# dumbpad.net
KiCad netlist of a schematic drawn in EAGLE
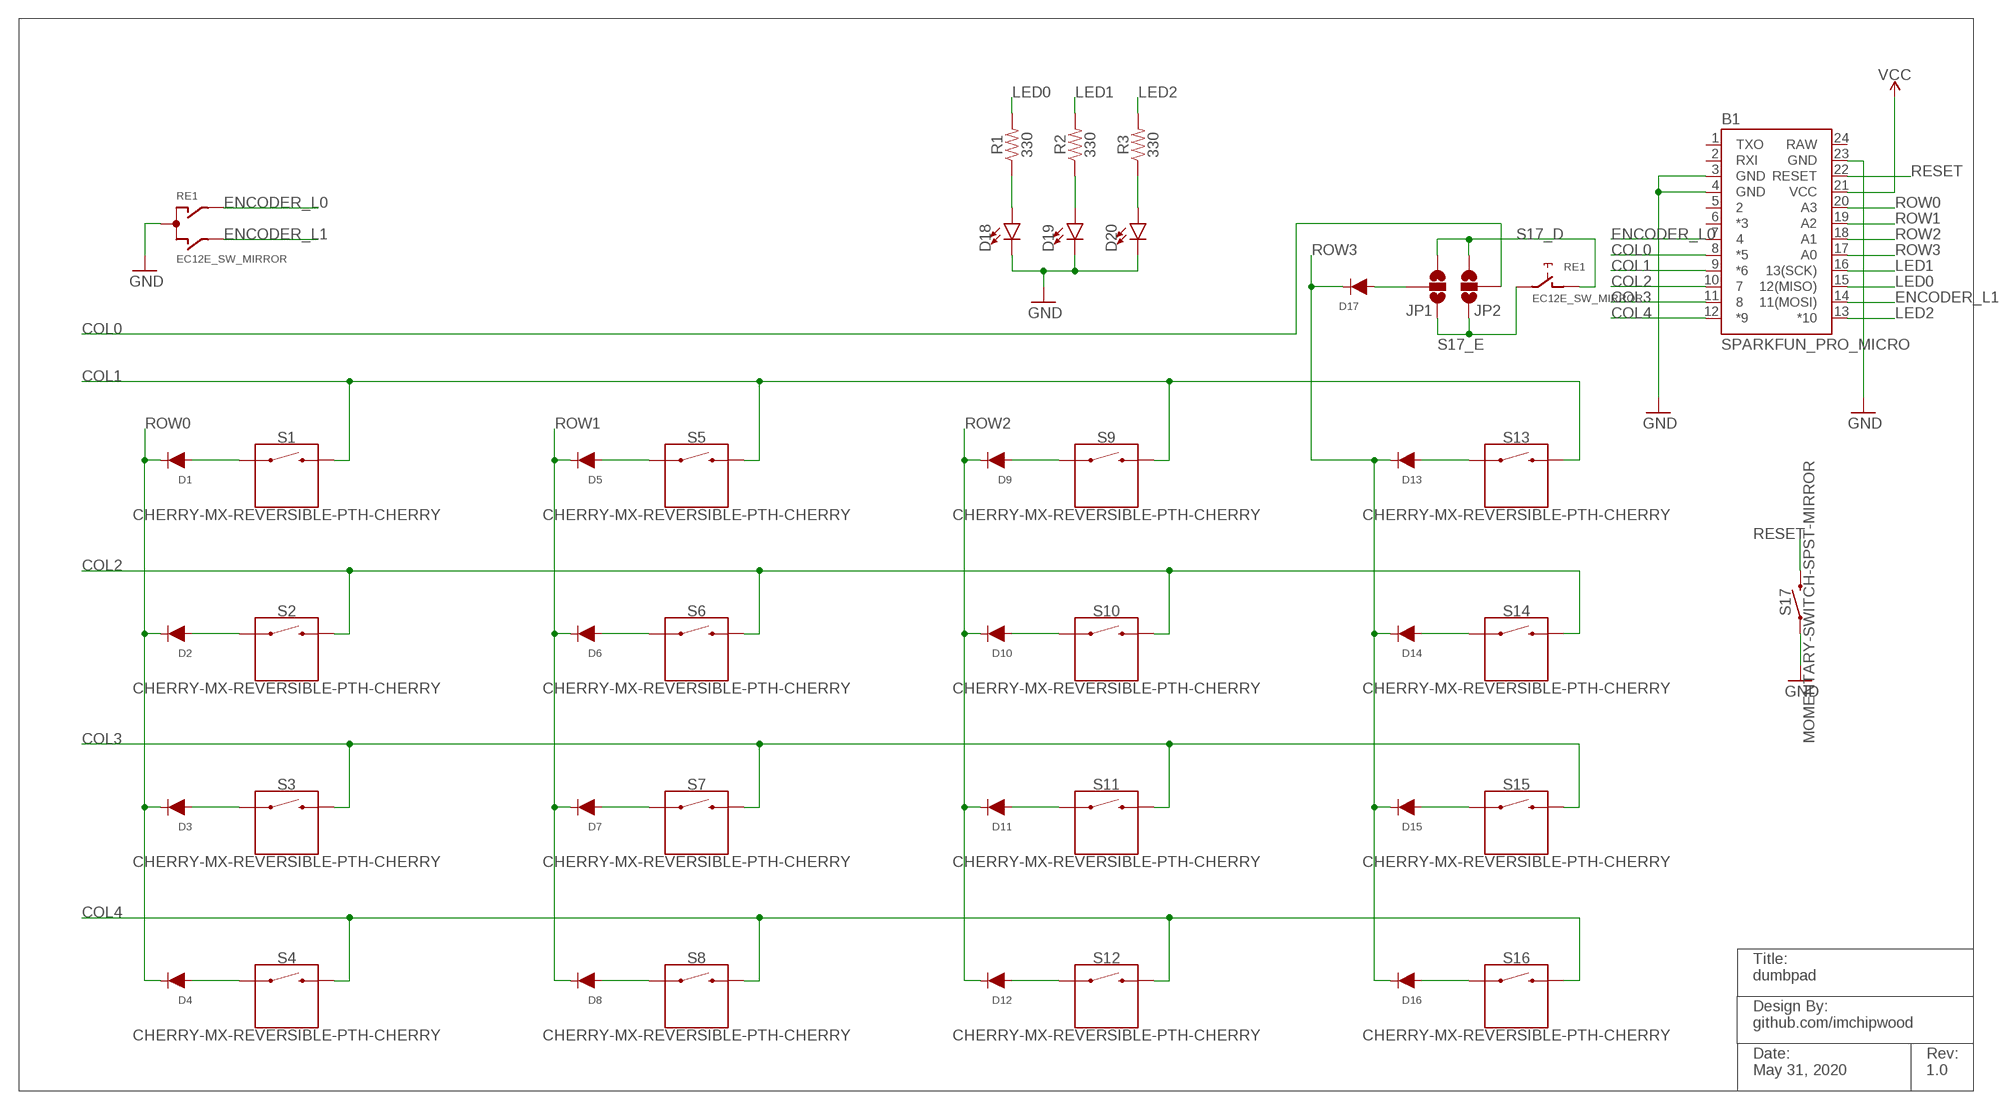
[diagram p0: schematic, sheet 1]

(export (version "E")
  (design (tool "Eeschema 10.0.6"))
  (components
    (comp (ref "B1")
      (value "SPARKFUN_PRO_MICRO")
      (footprint "eagle-import:SPARKFUN_PRO_MICRO")
      (libsource (lib "eagle-import") (part "SPARKFUN_PRO_MICRO"))
    )
    (comp (ref "D1")
      (value "DO-1N4148_MIRROR")
      (footprint "eagle-import:DO-1N4148_MIRROR")
      (libsource (lib "eagle-import") (part "DO-1N4148_MIRROR"))
    )
    (comp (ref "D2")
      (value "DO-1N4148_MIRROR")
      (footprint "eagle-import:DO-1N4148_MIRROR")
      (libsource (lib "eagle-import") (part "DO-1N4148_MIRROR"))
    )
    (comp (ref "D3")
      (value "DO-1N4148_MIRROR")
      (footprint "eagle-import:DO-1N4148_MIRROR")
      (libsource (lib "eagle-import") (part "DO-1N4148_MIRROR"))
    )
    (comp (ref "D4")
      (value "DO-1N4148_MIRROR")
      (footprint "eagle-import:DO-1N4148_MIRROR")
      (libsource (lib "eagle-import") (part "DO-1N4148_MIRROR"))
    )
    (comp (ref "D5")
      (value "DO-1N4148_MIRROR")
      (footprint "eagle-import:DO-1N4148_MIRROR")
      (libsource (lib "eagle-import") (part "DO-1N4148_MIRROR"))
    )
    (comp (ref "D6")
      (value "DO-1N4148_MIRROR")
      (footprint "eagle-import:DO-1N4148_MIRROR")
      (libsource (lib "eagle-import") (part "DO-1N4148_MIRROR"))
    )
    (comp (ref "D7")
      (value "DO-1N4148_MIRROR")
      (footprint "eagle-import:DO-1N4148_MIRROR")
      (libsource (lib "eagle-import") (part "DO-1N4148_MIRROR"))
    )
    (comp (ref "D8")
      (value "DO-1N4148_MIRROR")
      (footprint "eagle-import:DO-1N4148_MIRROR")
      (libsource (lib "eagle-import") (part "DO-1N4148_MIRROR"))
    )
    (comp (ref "D9")
      (value "DO-1N4148_MIRROR")
      (footprint "eagle-import:DO-1N4148_MIRROR")
      (libsource (lib "eagle-import") (part "DO-1N4148_MIRROR"))
    )
    (comp (ref "D10")
      (value "DO-1N4148_MIRROR")
      (footprint "eagle-import:DO-1N4148_MIRROR")
      (libsource (lib "eagle-import") (part "DO-1N4148_MIRROR"))
    )
    (comp (ref "D11")
      (value "DO-1N4148_MIRROR")
      (footprint "eagle-import:DO-1N4148_MIRROR")
      (libsource (lib "eagle-import") (part "DO-1N4148_MIRROR"))
    )
    (comp (ref "D12")
      (value "DO-1N4148_MIRROR")
      (footprint "eagle-import:DO-1N4148_MIRROR")
      (libsource (lib "eagle-import") (part "DO-1N4148_MIRROR"))
    )
    (comp (ref "D13")
      (value "DO-1N4148_MIRROR")
      (footprint "eagle-import:DO-1N4148_MIRROR")
      (libsource (lib "eagle-import") (part "DO-1N4148_MIRROR"))
    )
    (comp (ref "D14")
      (value "DO-1N4148_MIRROR")
      (footprint "eagle-import:DO-1N4148_MIRROR")
      (libsource (lib "eagle-import") (part "DO-1N4148_MIRROR"))
    )
    (comp (ref "D15")
      (value "DO-1N4148_MIRROR")
      (footprint "eagle-import:DO-1N4148_MIRROR")
      (libsource (lib "eagle-import") (part "DO-1N4148_MIRROR"))
    )
    (comp (ref "D16")
      (value "DO-1N4148_MIRROR")
      (footprint "eagle-import:DO-1N4148_MIRROR")
      (libsource (lib "eagle-import") (part "DO-1N4148_MIRROR"))
    )
    (comp (ref "D17")
      (value "DO-1N4148_MIRROR")
      (footprint "eagle-import:DO-1N4148_MIRROR")
      (libsource (lib "eagle-import") (part "DO-1N4148_MIRROR"))
    )
    (comp (ref "D18")
      (value "LED3MM")
      (footprint "eagle-import:LED_3MM")
      (libsource (lib "eagle-import") (part "LED3MM"))
    )
    (comp (ref "D19")
      (value "LED3MM")
      (footprint "eagle-import:LED_3MM")
      (libsource (lib "eagle-import") (part "LED3MM"))
    )
    (comp (ref "D20")
      (value "LED3MM")
      (footprint "eagle-import:LED_3MM")
      (libsource (lib "eagle-import") (part "LED3MM"))
    )
    (comp (ref "JP1")
      (value "JUMPER-SMT_3_NO_NO_SILK")
      (footprint "eagle-import:SMT-JUMPER_3_0-NO_TRACE_NO-SILK")
      (libsource (lib "eagle-import") (part "JUMPER-SMT_3_NO_NO_SILK"))
    )
    (comp (ref "JP2")
      (value "JUMPER-SMT_3_NO_NO_SILK")
      (footprint "eagle-import:SMT-JUMPER_3_0-NO_TRACE_NO-SILK")
      (libsource (lib "eagle-import") (part "JUMPER-SMT_3_NO_NO_SILK"))
    )
    (comp (ref "R1")
      (value "330")
      (footprint "eagle-import:AXIAL-0.3_MIRROR")
      (libsource (lib "eagle-import") (part "RESISTOR_MIRROR"))
    )
    (comp (ref "R2")
      (value "330")
      (footprint "eagle-import:AXIAL-0.3_MIRROR")
      (libsource (lib "eagle-import") (part "RESISTOR_MIRROR"))
    )
    (comp (ref "R3")
      (value "330")
      (footprint "eagle-import:AXIAL-0.3_MIRROR")
      (libsource (lib "eagle-import") (part "RESISTOR_MIRROR"))
    )
    (comp (ref "RE1")
      (value "EC12E_SW_MIRROR")
      (footprint "eagle-import:ALPS_EC12E_SW_MIRROR")
      (fields (field (name "MPN") "EC12E2424407"))
      (libsource (lib "eagle-import") (part "EC12E_SW_MIRROR"))
    )
    (comp (ref "S1")
      (value "CHERRY-MX-REVERSIBLE-PTH-CHERRY")
      (footprint "eagle-import:CHERRY-MX-REVERSIBLE")
      (libsource (lib "eagle-import") (part "CHERRY-MX-REVERSIBLE-PTH-CHERRY"))
    )
    (comp (ref "S2")
      (value "CHERRY-MX-REVERSIBLE-PTH-CHERRY")
      (footprint "eagle-import:CHERRY-MX-REVERSIBLE")
      (libsource (lib "eagle-import") (part "CHERRY-MX-REVERSIBLE-PTH-CHERRY"))
    )
    (comp (ref "S3")
      (value "CHERRY-MX-REVERSIBLE-PTH-CHERRY")
      (footprint "eagle-import:CHERRY-MX-REVERSIBLE")
      (libsource (lib "eagle-import") (part "CHERRY-MX-REVERSIBLE-PTH-CHERRY"))
    )
    (comp (ref "S4")
      (value "CHERRY-MX-REVERSIBLE-PTH-CHERRY")
      (footprint "eagle-import:CHERRY-MX-REVERSIBLE")
      (libsource (lib "eagle-import") (part "CHERRY-MX-REVERSIBLE-PTH-CHERRY"))
    )
    (comp (ref "S5")
      (value "CHERRY-MX-REVERSIBLE-PTH-CHERRY")
      (footprint "eagle-import:CHERRY-MX-REVERSIBLE")
      (libsource (lib "eagle-import") (part "CHERRY-MX-REVERSIBLE-PTH-CHERRY"))
    )
    (comp (ref "S6")
      (value "CHERRY-MX-REVERSIBLE-PTH-CHERRY")
      (footprint "eagle-import:CHERRY-MX-REVERSIBLE")
      (libsource (lib "eagle-import") (part "CHERRY-MX-REVERSIBLE-PTH-CHERRY"))
    )
    (comp (ref "S7")
      (value "CHERRY-MX-REVERSIBLE-PTH-CHERRY")
      (footprint "eagle-import:CHERRY-MX-REVERSIBLE")
      (libsource (lib "eagle-import") (part "CHERRY-MX-REVERSIBLE-PTH-CHERRY"))
    )
    (comp (ref "S8")
      (value "CHERRY-MX-REVERSIBLE-PTH-CHERRY")
      (footprint "eagle-import:CHERRY-MX-REVERSIBLE")
      (libsource (lib "eagle-import") (part "CHERRY-MX-REVERSIBLE-PTH-CHERRY"))
    )
    (comp (ref "S9")
      (value "CHERRY-MX-REVERSIBLE-PTH-CHERRY")
      (footprint "eagle-import:CHERRY-MX-REVERSIBLE")
      (libsource (lib "eagle-import") (part "CHERRY-MX-REVERSIBLE-PTH-CHERRY"))
    )
    (comp (ref "S10")
      (value "CHERRY-MX-REVERSIBLE-PTH-CHERRY")
      (footprint "eagle-import:CHERRY-MX-REVERSIBLE")
      (libsource (lib "eagle-import") (part "CHERRY-MX-REVERSIBLE-PTH-CHERRY"))
    )
    (comp (ref "S11")
      (value "CHERRY-MX-REVERSIBLE-PTH-CHERRY")
      (footprint "eagle-import:CHERRY-MX-REVERSIBLE")
      (libsource (lib "eagle-import") (part "CHERRY-MX-REVERSIBLE-PTH-CHERRY"))
    )
    (comp (ref "S12")
      (value "CHERRY-MX-REVERSIBLE-PTH-CHERRY")
      (footprint "eagle-import:CHERRY-MX-REVERSIBLE")
      (libsource (lib "eagle-import") (part "CHERRY-MX-REVERSIBLE-PTH-CHERRY"))
    )
    (comp (ref "S13")
      (value "CHERRY-MX-REVERSIBLE-PTH-CHERRY")
      (footprint "eagle-import:CHERRY-MX-REVERSIBLE")
      (libsource (lib "eagle-import") (part "CHERRY-MX-REVERSIBLE-PTH-CHERRY"))
    )
    (comp (ref "S14")
      (value "CHERRY-MX-REVERSIBLE-PTH-CHERRY")
      (footprint "eagle-import:CHERRY-MX-REVERSIBLE")
      (libsource (lib "eagle-import") (part "CHERRY-MX-REVERSIBLE-PTH-CHERRY"))
    )
    (comp (ref "S15")
      (value "CHERRY-MX-REVERSIBLE-PTH-CHERRY")
      (footprint "eagle-import:CHERRY-MX-REVERSIBLE")
      (libsource (lib "eagle-import") (part "CHERRY-MX-REVERSIBLE-PTH-CHERRY"))
    )
    (comp (ref "S16")
      (value "CHERRY-MX-REVERSIBLE-PTH-CHERRY")
      (footprint "eagle-import:CHERRY-MX-REVERSIBLE")
      (libsource (lib "eagle-import") (part "CHERRY-MX-REVERSIBLE-PTH-CHERRY"))
    )
    (comp (ref "S17")
      (value "MOMENTARY-SWITCH-SPST-MIRROR")
      (footprint "eagle-import:TACTILE_SWITCH_PTH_6.0MM_MIRROR")
      (libsource (lib "eagle-import") (part "MOMENTARY-SWITCH-SPST-MIRROR"))
    )
  )
  (nets
    (net (code "1") (name "/COL0") (class "Default")
      (node (ref "B1") (pin "8") (pinfunction "*5_8") (pintype "bidirectional"))
      (node (ref "JP2") (pin "2") (pinfunction "2_2") (pintype "passive"))
    )
    (net (code "2") (name "/COL1") (class "Default")
      (node (ref "B1") (pin "9") (pinfunction "*6_9") (pintype "bidirectional"))
      (node (ref "S1") (pin "S2_0") (pinfunction "2_S2_0") (pintype "passive"))
      (node (ref "S1") (pin "S2_1") (pinfunction "2_S2_1") (pintype "passive"))
      (node (ref "S13") (pin "S2_0") (pinfunction "2_S2_0") (pintype "passive"))
      (node (ref "S13") (pin "S2_1") (pinfunction "2_S2_1") (pintype "passive"))
      (node (ref "S5") (pin "S2_0") (pinfunction "2_S2_0") (pintype "passive"))
      (node (ref "S5") (pin "S2_1") (pinfunction "2_S2_1") (pintype "passive"))
      (node (ref "S9") (pin "S2_0") (pinfunction "2_S2_0") (pintype "passive"))
      (node (ref "S9") (pin "S2_1") (pinfunction "2_S2_1") (pintype "passive"))
    )
    (net (code "3") (name "/COL2") (class "Default")
      (node (ref "B1") (pin "10") (pinfunction "7_10") (pintype "bidirectional"))
      (node (ref "S10") (pin "S2_0") (pinfunction "2_S2_0") (pintype "passive"))
      (node (ref "S10") (pin "S2_1") (pinfunction "2_S2_1") (pintype "passive"))
      (node (ref "S14") (pin "S2_0") (pinfunction "2_S2_0") (pintype "passive"))
      (node (ref "S14") (pin "S2_1") (pinfunction "2_S2_1") (pintype "passive"))
      (node (ref "S2") (pin "S2_0") (pinfunction "2_S2_0") (pintype "passive"))
      (node (ref "S2") (pin "S2_1") (pinfunction "2_S2_1") (pintype "passive"))
      (node (ref "S6") (pin "S2_0") (pinfunction "2_S2_0") (pintype "passive"))
      (node (ref "S6") (pin "S2_1") (pinfunction "2_S2_1") (pintype "passive"))
    )
    (net (code "4") (name "/COL3") (class "Default")
      (node (ref "B1") (pin "11") (pinfunction "8_11") (pintype "bidirectional"))
      (node (ref "S11") (pin "S2_0") (pinfunction "2_S2_0") (pintype "passive"))
      (node (ref "S11") (pin "S2_1") (pinfunction "2_S2_1") (pintype "passive"))
      (node (ref "S15") (pin "S2_0") (pinfunction "2_S2_0") (pintype "passive"))
      (node (ref "S15") (pin "S2_1") (pinfunction "2_S2_1") (pintype "passive"))
      (node (ref "S3") (pin "S2_0") (pinfunction "2_S2_0") (pintype "passive"))
      (node (ref "S3") (pin "S2_1") (pinfunction "2_S2_1") (pintype "passive"))
      (node (ref "S7") (pin "S2_0") (pinfunction "2_S2_0") (pintype "passive"))
      (node (ref "S7") (pin "S2_1") (pinfunction "2_S2_1") (pintype "passive"))
    )
    (net (code "5") (name "/COL4") (class "Default")
      (node (ref "B1") (pin "12") (pinfunction "*9_12") (pintype "bidirectional"))
      (node (ref "S12") (pin "S2_0") (pinfunction "2_S2_0") (pintype "passive"))
      (node (ref "S12") (pin "S2_1") (pinfunction "2_S2_1") (pintype "passive"))
      (node (ref "S16") (pin "S2_0") (pinfunction "2_S2_0") (pintype "passive"))
      (node (ref "S16") (pin "S2_1") (pinfunction "2_S2_1") (pintype "passive"))
      (node (ref "S4") (pin "S2_0") (pinfunction "2_S2_0") (pintype "passive"))
      (node (ref "S4") (pin "S2_1") (pinfunction "2_S2_1") (pintype "passive"))
      (node (ref "S8") (pin "S2_0") (pinfunction "2_S2_0") (pintype "passive"))
      (node (ref "S8") (pin "S2_1") (pinfunction "2_S2_1") (pintype "passive"))
    )
    (net (code "6") (name "/ENCODER_L0") (class "Default")
      (node (ref "B1") (pin "7") (pinfunction "4_7") (pintype "bidirectional"))
      (node (ref "RE1") (pin "A") (pinfunction "A_A") (pintype "passive"))
    )
    (net (code "7") (name "/ENCODER_L1") (class "Default")
      (node (ref "B1") (pin "14") (pinfunction "11(MOSI)_14") (pintype "bidirectional"))
      (node (ref "RE1") (pin "B") (pinfunction "B_B") (pintype "passive"))
    )
    (net (code "8") (name "/LED0") (class "Default")
      (node (ref "B1") (pin "15") (pinfunction "12(MISO)_15") (pintype "bidirectional"))
      (node (ref "R1") (pin "P$2") (pinfunction "2_P$2") (pintype "passive"))
    )
    (net (code "9") (name "/LED1") (class "Default")
      (node (ref "B1") (pin "16") (pinfunction "13(SCK)_16") (pintype "bidirectional"))
      (node (ref "R2") (pin "P$2") (pinfunction "2_P$2") (pintype "passive"))
    )
    (net (code "10") (name "/LED2") (class "Default")
      (node (ref "B1") (pin "13") (pinfunction "*10_13") (pintype "bidirectional"))
      (node (ref "R3") (pin "P$2") (pinfunction "2_P$2") (pintype "passive"))
    )
    (net (code "11") (name "/RAW") (class "Default")
      (node (ref "B1") (pin "24") (pinfunction "RAW_24") (pintype "power_in"))
    )
    (net (code "12") (name "/RESET") (class "Default")
      (node (ref "B1") (pin "22") (pinfunction "RESET_22") (pintype "bidirectional"))
      (node (ref "S17") (pin "2") (pinfunction "2_2") (pintype "passive"))
    )
    (net (code "13") (name "/ROW0") (class "Default")
      (node (ref "B1") (pin "20") (pinfunction "A3_20") (pintype "bidirectional"))
      (node (ref "D1") (pin "C") (pinfunction "C_C") (pintype "passive"))
      (node (ref "D2") (pin "C") (pinfunction "C_C") (pintype "passive"))
      (node (ref "D3") (pin "C") (pinfunction "C_C") (pintype "passive"))
      (node (ref "D4") (pin "C") (pinfunction "C_C") (pintype "passive"))
    )
    (net (code "14") (name "/ROW1") (class "Default")
      (node (ref "B1") (pin "19") (pinfunction "A2_19") (pintype "bidirectional"))
      (node (ref "D5") (pin "C") (pinfunction "C_C") (pintype "passive"))
      (node (ref "D6") (pin "C") (pinfunction "C_C") (pintype "passive"))
      (node (ref "D7") (pin "C") (pinfunction "C_C") (pintype "passive"))
      (node (ref "D8") (pin "C") (pinfunction "C_C") (pintype "passive"))
    )
    (net (code "15") (name "/ROW2") (class "Default")
      (node (ref "B1") (pin "18") (pinfunction "A1_18") (pintype "bidirectional"))
      (node (ref "D10") (pin "C") (pinfunction "C_C") (pintype "passive"))
      (node (ref "D11") (pin "C") (pinfunction "C_C") (pintype "passive"))
      (node (ref "D12") (pin "C") (pinfunction "C_C") (pintype "passive"))
      (node (ref "D9") (pin "C") (pinfunction "C_C") (pintype "passive"))
    )
    (net (code "16") (name "/ROW3") (class "Default")
      (node (ref "B1") (pin "17") (pinfunction "A0_17") (pintype "bidirectional"))
      (node (ref "D13") (pin "C") (pinfunction "C_C") (pintype "passive"))
      (node (ref "D14") (pin "C") (pinfunction "C_C") (pintype "passive"))
      (node (ref "D15") (pin "C") (pinfunction "C_C") (pintype "passive"))
      (node (ref "D16") (pin "C") (pinfunction "C_C") (pintype "passive"))
      (node (ref "D17") (pin "C") (pinfunction "C_C") (pintype "passive"))
    )
    (net (code "17") (name "/S17_D") (class "Default")
      (node (ref "JP1") (pin "1") (pinfunction "1_1") (pintype "passive"))
      (node (ref "JP2") (pin "3") (pinfunction "3_3") (pintype "passive"))
      (node (ref "RE1") (pin "D") (pinfunction "1_D") (pintype "passive"))
    )
    (net (code "18") (name "/S17_E") (class "Default")
      (node (ref "JP1") (pin "3") (pinfunction "3_3") (pintype "passive"))
      (node (ref "JP2") (pin "1") (pinfunction "1_1") (pintype "passive"))
      (node (ref "RE1") (pin "E") (pinfunction "2_E") (pintype "passive"))
    )
    (net (code "19") (name "GND") (class "Default")
      (node (ref "B1") (pin "23") (pinfunction "GND_23") (pintype "power_in"))
      (node (ref "B1") (pin "3") (pinfunction "GND_3") (pintype "power_in"))
      (node (ref "B1") (pin "4") (pinfunction "GND_4") (pintype "power_in"))
      (node (ref "D18") (pin "K") (pinfunction "C_K") (pintype "passive"))
      (node (ref "D19") (pin "K") (pinfunction "C_K") (pintype "passive"))
      (node (ref "D20") (pin "K") (pinfunction "C_K") (pintype "passive"))
      (node (ref "RE1") (pin "C") (pinfunction "C_C") (pintype "passive"))
      (node (ref "S17") (pin "1") (pinfunction "1_1") (pintype "passive"))
    )
    (net (code "20") (name "Net-(D1-PadA)") (class "Default")
      (node (ref "D1") (pin "A") (pinfunction "A_A") (pintype "passive"))
      (node (ref "S1") (pin "S1_0") (pinfunction "1_S1_0") (pintype "passive"))
      (node (ref "S1") (pin "S1_1") (pinfunction "1_S1_1") (pintype "passive"))
    )
    (net (code "21") (name "Net-(D2-PadA)") (class "Default")
      (node (ref "D2") (pin "A") (pinfunction "A_A") (pintype "passive"))
      (node (ref "S2") (pin "S1_0") (pinfunction "1_S1_0") (pintype "passive"))
      (node (ref "S2") (pin "S1_1") (pinfunction "1_S1_1") (pintype "passive"))
    )
    (net (code "22") (name "Net-(D3-PadA)") (class "Default")
      (node (ref "D3") (pin "A") (pinfunction "A_A") (pintype "passive"))
      (node (ref "S3") (pin "S1_0") (pinfunction "1_S1_0") (pintype "passive"))
      (node (ref "S3") (pin "S1_1") (pinfunction "1_S1_1") (pintype "passive"))
    )
    (net (code "23") (name "Net-(D4-PadA)") (class "Default")
      (node (ref "D4") (pin "A") (pinfunction "A_A") (pintype "passive"))
      (node (ref "S4") (pin "S1_0") (pinfunction "1_S1_0") (pintype "passive"))
      (node (ref "S4") (pin "S1_1") (pinfunction "1_S1_1") (pintype "passive"))
    )
    (net (code "24") (name "Net-(D5-PadA)") (class "Default")
      (node (ref "D5") (pin "A") (pinfunction "A_A") (pintype "passive"))
      (node (ref "S5") (pin "S1_0") (pinfunction "1_S1_0") (pintype "passive"))
      (node (ref "S5") (pin "S1_1") (pinfunction "1_S1_1") (pintype "passive"))
    )
    (net (code "25") (name "Net-(D6-PadA)") (class "Default")
      (node (ref "D6") (pin "A") (pinfunction "A_A") (pintype "passive"))
      (node (ref "S6") (pin "S1_0") (pinfunction "1_S1_0") (pintype "passive"))
      (node (ref "S6") (pin "S1_1") (pinfunction "1_S1_1") (pintype "passive"))
    )
    (net (code "26") (name "Net-(D7-PadA)") (class "Default")
      (node (ref "D7") (pin "A") (pinfunction "A_A") (pintype "passive"))
      (node (ref "S7") (pin "S1_0") (pinfunction "1_S1_0") (pintype "passive"))
      (node (ref "S7") (pin "S1_1") (pinfunction "1_S1_1") (pintype "passive"))
    )
    (net (code "27") (name "Net-(D8-PadA)") (class "Default")
      (node (ref "D8") (pin "A") (pinfunction "A_A") (pintype "passive"))
      (node (ref "S8") (pin "S1_0") (pinfunction "1_S1_0") (pintype "passive"))
      (node (ref "S8") (pin "S1_1") (pinfunction "1_S1_1") (pintype "passive"))
    )
    (net (code "28") (name "Net-(D9-PadA)") (class "Default")
      (node (ref "D9") (pin "A") (pinfunction "A_A") (pintype "passive"))
      (node (ref "S9") (pin "S1_0") (pinfunction "1_S1_0") (pintype "passive"))
      (node (ref "S9") (pin "S1_1") (pinfunction "1_S1_1") (pintype "passive"))
    )
    (net (code "29") (name "Net-(D10-PadA)") (class "Default")
      (node (ref "D10") (pin "A") (pinfunction "A_A") (pintype "passive"))
      (node (ref "S10") (pin "S1_0") (pinfunction "1_S1_0") (pintype "passive"))
      (node (ref "S10") (pin "S1_1") (pinfunction "1_S1_1") (pintype "passive"))
    )
    (net (code "30") (name "Net-(D11-PadA)") (class "Default")
      (node (ref "D11") (pin "A") (pinfunction "A_A") (pintype "passive"))
      (node (ref "S11") (pin "S1_0") (pinfunction "1_S1_0") (pintype "passive"))
      (node (ref "S11") (pin "S1_1") (pinfunction "1_S1_1") (pintype "passive"))
    )
    (net (code "31") (name "Net-(D12-PadA)") (class "Default")
      (node (ref "D12") (pin "A") (pinfunction "A_A") (pintype "passive"))
      (node (ref "S12") (pin "S1_0") (pinfunction "1_S1_0") (pintype "passive"))
      (node (ref "S12") (pin "S1_1") (pinfunction "1_S1_1") (pintype "passive"))
    )
    (net (code "32") (name "Net-(D13-PadA)") (class "Default")
      (node (ref "D13") (pin "A") (pinfunction "A_A") (pintype "passive"))
      (node (ref "S13") (pin "S1_0") (pinfunction "1_S1_0") (pintype "passive"))
      (node (ref "S13") (pin "S1_1") (pinfunction "1_S1_1") (pintype "passive"))
    )
    (net (code "33") (name "Net-(D14-PadA)") (class "Default")
      (node (ref "D14") (pin "A") (pinfunction "A_A") (pintype "passive"))
      (node (ref "S14") (pin "S1_0") (pinfunction "1_S1_0") (pintype "passive"))
      (node (ref "S14") (pin "S1_1") (pinfunction "1_S1_1") (pintype "passive"))
    )
    (net (code "34") (name "Net-(D15-PadA)") (class "Default")
      (node (ref "D15") (pin "A") (pinfunction "A_A") (pintype "passive"))
      (node (ref "S15") (pin "S1_0") (pinfunction "1_S1_0") (pintype "passive"))
      (node (ref "S15") (pin "S1_1") (pinfunction "1_S1_1") (pintype "passive"))
    )
    (net (code "35") (name "Net-(D16-PadA)") (class "Default")
      (node (ref "D16") (pin "A") (pinfunction "A_A") (pintype "passive"))
      (node (ref "S16") (pin "S1_0") (pinfunction "1_S1_0") (pintype "passive"))
      (node (ref "S16") (pin "S1_1") (pinfunction "1_S1_1") (pintype "passive"))
    )
    (net (code "36") (name "Net-(D17-PadA)") (class "Default")
      (node (ref "D17") (pin "A") (pinfunction "A_A") (pintype "passive"))
      (node (ref "JP1") (pin "2") (pinfunction "2_2") (pintype "passive"))
    )
    (net (code "37") (name "Net-(R1-1)") (class "Default")
      (node (ref "D18") (pin "A") (pinfunction "A_A") (pintype "passive"))
      (node (ref "R1") (pin "P$1") (pinfunction "1_P$1") (pintype "passive"))
    )
    (net (code "38") (name "Net-(R2-1)") (class "Default")
      (node (ref "D19") (pin "A") (pinfunction "A_A") (pintype "passive"))
      (node (ref "R2") (pin "P$1") (pinfunction "1_P$1") (pintype "passive"))
    )
    (net (code "39") (name "Net-(R3-1)") (class "Default")
      (node (ref "D20") (pin "A") (pinfunction "A_A") (pintype "passive"))
      (node (ref "R3") (pin "P$1") (pinfunction "1_P$1") (pintype "passive"))
    )
    (net (code "40") (name "VCC") (class "Default")
      (node (ref "B1") (pin "21") (pinfunction "VCC_21") (pintype "power_in"))
    )
    (net (code "41") (name "unconnected-(B1-*3-Pad6)") (class "Default")
      (node (ref "B1") (pin "6") (pinfunction "*3_6") (pintype "bidirectional"))
    )
    (net (code "42") (name "unconnected-(B1-2-Pad5)") (class "Default")
      (node (ref "B1") (pin "5") (pinfunction "2_5") (pintype "bidirectional"))
    )
    (net (code "43") (name "unconnected-(B1-RXI-Pad2)") (class "Default")
      (node (ref "B1") (pin "2") (pinfunction "RXI_2") (pintype "bidirectional"))
    )
    (net (code "44") (name "unconnected-(B1-TXO-Pad1)") (class "Default")
      (node (ref "B1") (pin "1") (pinfunction "TXO_1") (pintype "bidirectional"))
    )
  )
)
